# SCH_esig_2025-06-15.net
KiCad netlist of a schematic drawn in EasyEDA
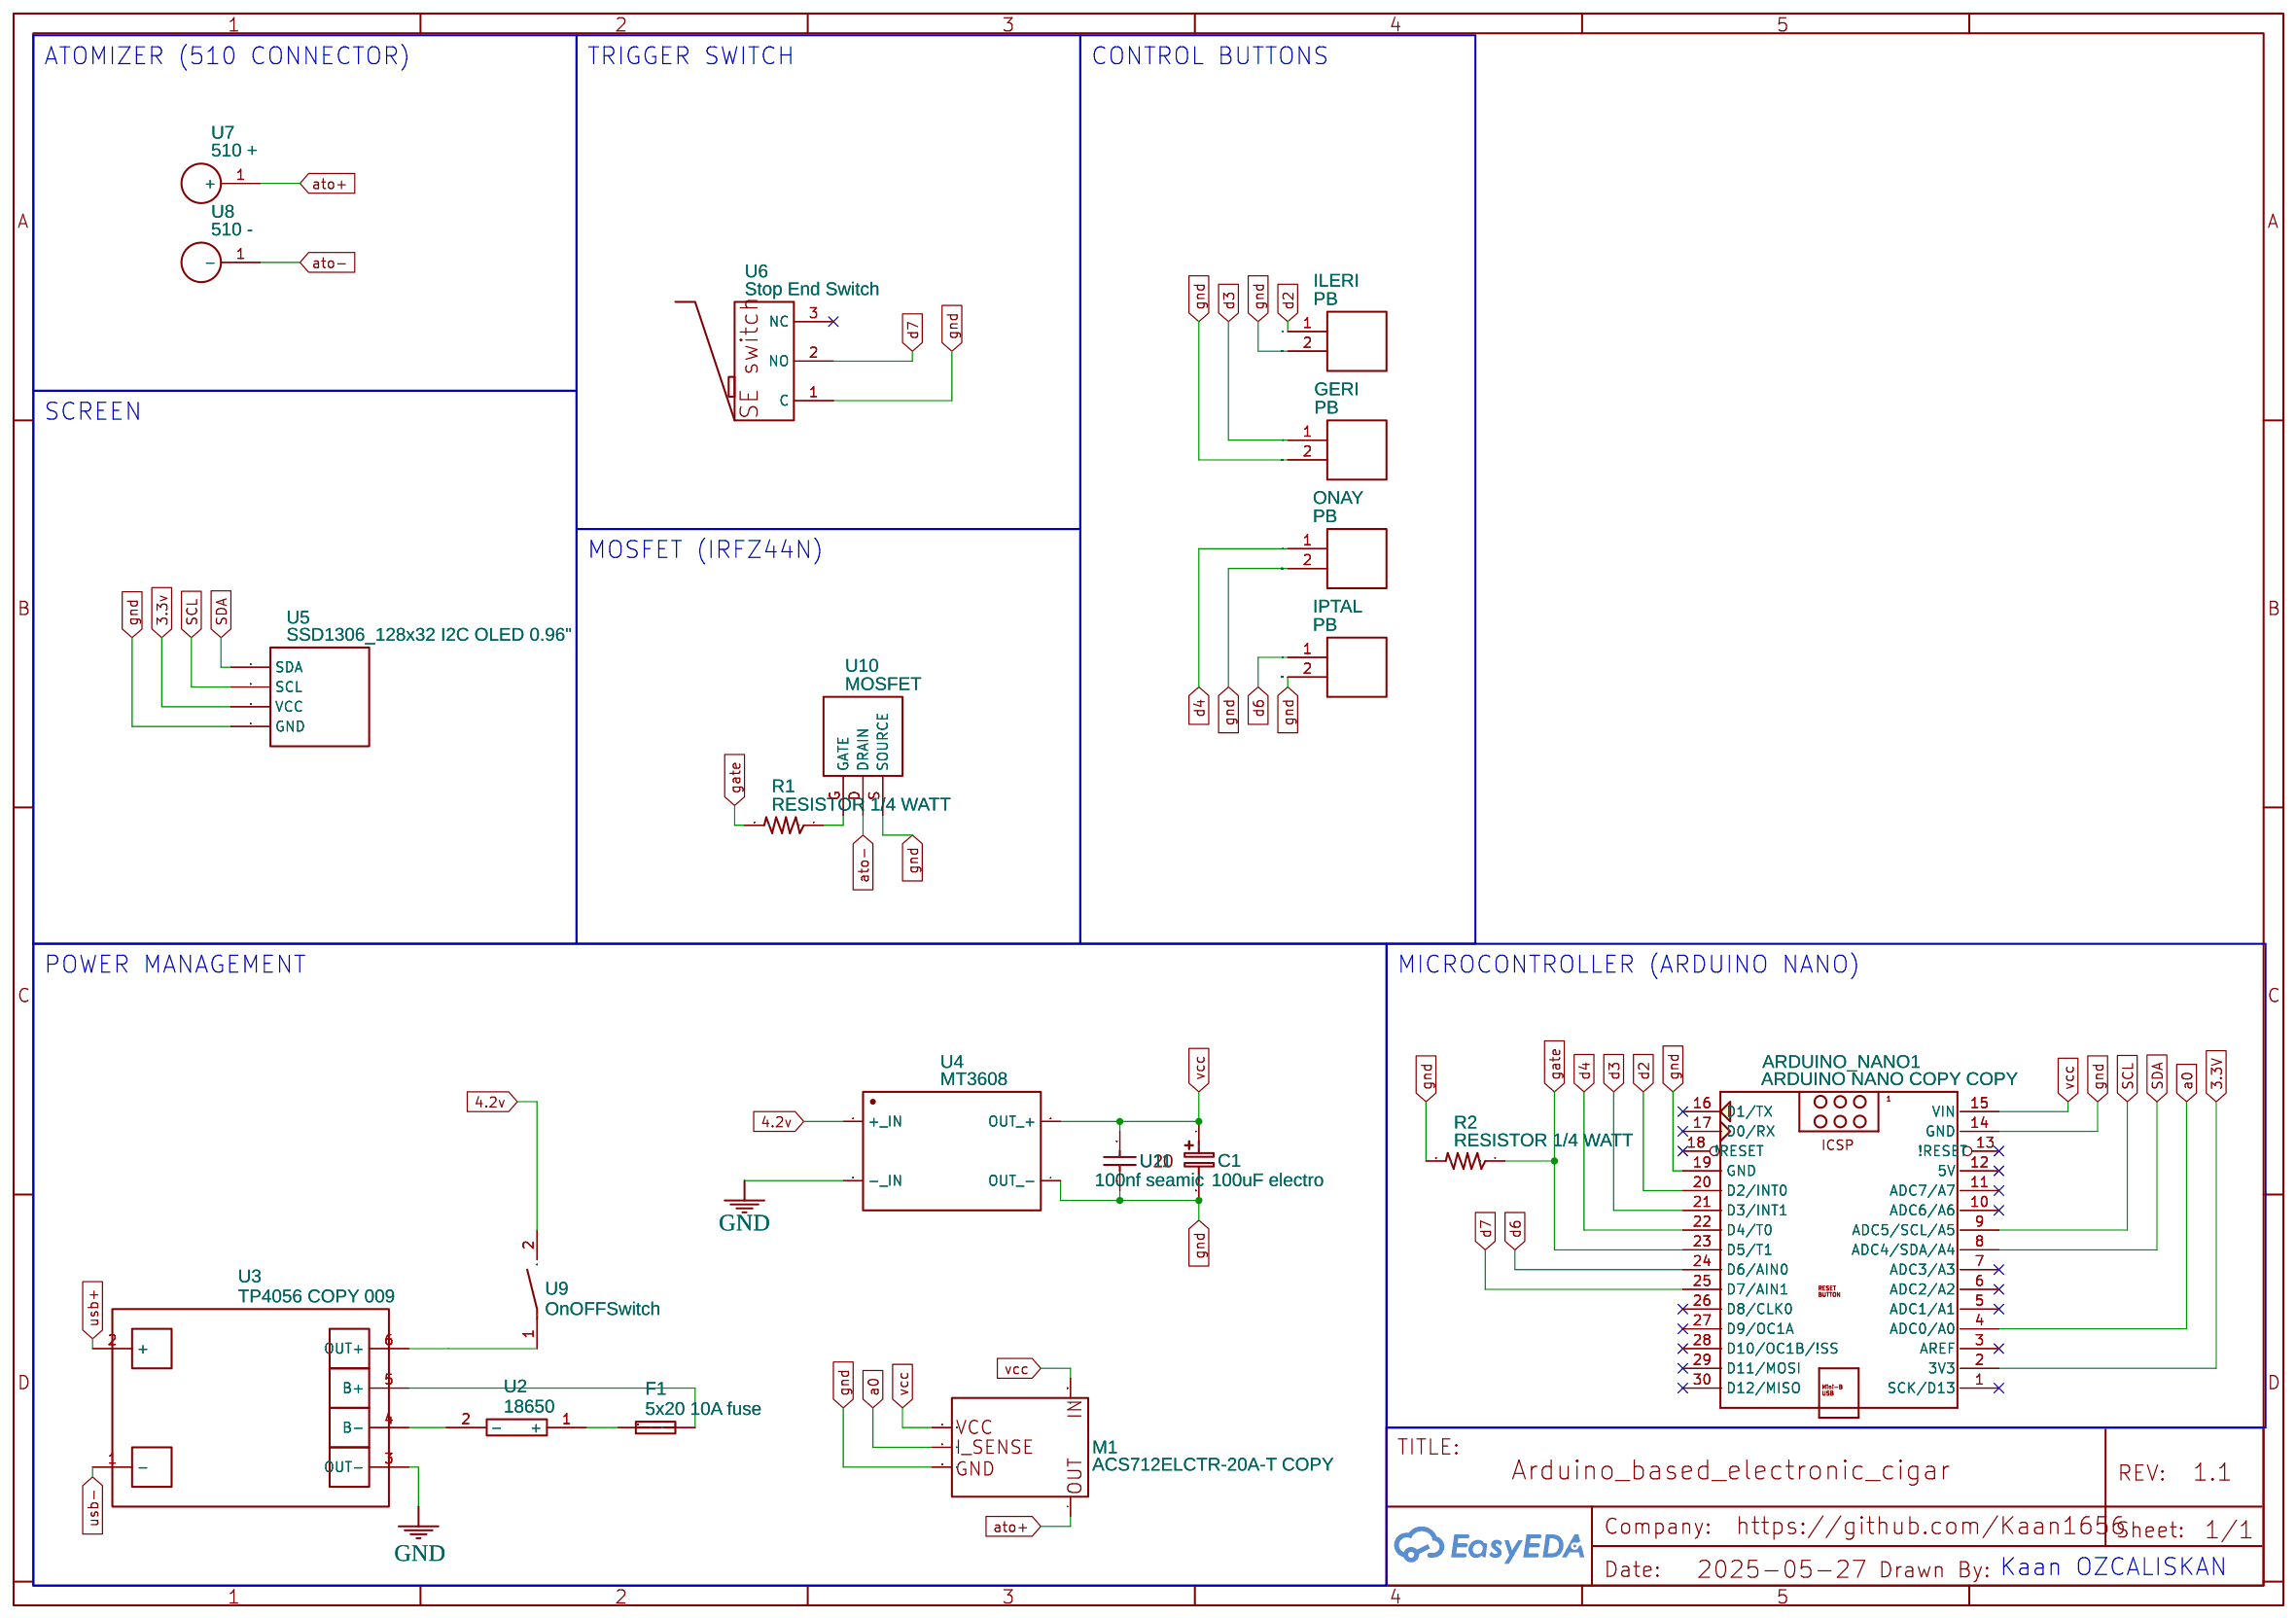
[diagram p0: schematic sheet]

(export (version "E")
  (design (tool "Eeschema 10.0.6"))
  (components
    (comp (ref "ARDUINO_NANO1")
      (value "ARDUINO NANO COPY COPY")
      (libsource (lib "") (part "ARDUINO NANO COPY COPY"))
    )
    (comp (ref "C1") (value "100uF electro") (libsource (lib "") (part "ELECTROLITIC_10MM_20.5MM")))
    (comp (ref "F1") (value "5x20 10A fuse") (libsource (lib "") (part "GLASS_FUSE_5X20")))
    (comp (ref "GERI") (value "PB") (libsource (lib "") (part "MY pushbutton_3")))
    (comp (ref "ILERI") (value "PB") (libsource (lib "") (part "MY pushbutton_2")))
    (comp (ref "IPTAL") (value "PB") (libsource (lib "") (part "MY pushbutton_1")))
    (comp (ref "M1") (value "ACS712ELCTR-20A-T COPY") (libsource (lib "") (part "ACS712ELCTR-20A-T COPY")))
    (comp (ref "ONAY") (value "PB") (libsource (lib "") (part "MY pushbutton")))
    (comp (ref "R1") (value "RESISTOR 1/4 WATT") (libsource (lib "") (part "RESISTOR 1/4 WATT TH Ω")))
    (comp (ref "R2") (value "RESISTOR 1/4 WATT") (libsource (lib "") (part "RESISTOR 1/4 WATT TH Ω")))
    (comp (ref "U2") (value "18650") (libsource (lib "") (part "18650_Mount")))
    (comp (ref "U3") (value "TP4056 COPY 009") (libsource (lib "") (part "TP4056 COPY 009")))
    (comp (ref "U4")
      (value "MT3608")
      (fields
        (field (name "Manufacturer Part") "MT3806 DC-DC Step Up")
        (field (name "Manufacturer") "NoName")
      )
      (libsource (lib "") (part "MT3806"))
    )
    (comp (ref "U5")
      (value "SSD1306_128x32 I2C OLED 0.96\"")
      (libsource (lib "") (part "SSD1306_128x32 I2C OLED 0.96{dblquote}"))
    )
    (comp (ref "U6") (value "Stop End Switch") (libsource (lib "") (part "Stop End Switch")))
    (comp (ref "U7") (value "510 +") (libsource (lib "") (part "wire hole 20AWG")))
    (comp (ref "U8") (value "510 -") (libsource (lib "") (part "wire hole 20AWG_1")))
    (comp (ref "U9") (value "OnOFFSwitch") (libsource (lib "") (part "OnOFFSwitch")))
    (comp (ref "U10") (value "MOSFET") (libsource (lib "") (part "MOSFET")))
    (comp (ref "U11") (value "100nf seamic") (libsource (lib "") (part "Large seramic capacitor")))
  )
  (nets
    (net (code "1") (name "3.3V") (class "Default")
      (node (ref "ARDUINO_NANO1") (pin "2") (pinfunction "3V3_2") (pintype "bidirectional"))
    )
    (net (code "2") (name "3.3v") (class "Default")
      (node (ref "U5") (pin "3") (pinfunction "VCC_3") (pintype "unspecified"))
    )
    (net (code "3") (name "4.2v") (class "Default")
      (node (ref "U4") (pin "1") (pinfunction "+_IN_1") (pintype "unspecified"))
      (node (ref "U9") (pin "2") (pinfunction "2_2") (pintype "unspecified"))
    )
    (net (code "4") (name "GND") (class "Default")
      (node (ref "U3") (pin "3") (pinfunction "OUT-_3") (pintype "unspecified"))
      (node (ref "U4") (pin "2") (pinfunction "-_IN_2") (pintype "unspecified"))
    )
    (net (code "5") (name "Net-(U2-+)") (class "Default")
      (node (ref "F1") (pin "2") (pinfunction "2_2") (pintype "unspecified"))
      (node (ref "U2") (pin "1") (pinfunction "+_1") (pintype "unspecified"))
    )
    (net (code "6") (name "Net-(U2--)") (class "Default")
      (node (ref "U2") (pin "2") (pinfunction "-_2") (pintype "unspecified"))
      (node (ref "U3") (pin "4") (pinfunction "B-_4") (pintype "unspecified"))
    )
    (net (code "7") (name "Net-(U3-B+)") (class "Default")
      (node (ref "F1") (pin "1") (pinfunction "1_1") (pintype "unspecified"))
      (node (ref "U3") (pin "5") (pinfunction "B+_5") (pintype "unspecified"))
    )
    (net (code "8") (name "Net-(U3-OUT+)") (class "Default")
      (node (ref "U3") (pin "6") (pinfunction "OUT+_6") (pintype "unspecified"))
      (node (ref "U9") (pin "1") (pinfunction "1_1") (pintype "unspecified"))
    )
    (net (code "9") (name "Net-(U10-GATE)") (class "Default")
      (node (ref "R1") (pin "1") (pinfunction "1_1") (pintype "unspecified"))
      (node (ref "U10") (pin "G") (pinfunction "GATE_G") (pintype "unspecified"))
    )
    (net (code "10") (name "SCL") (class "Default")
      (node (ref "ARDUINO_NANO1") (pin "9") (pinfunction "ADC5/SCL/A5_9") (pintype "bidirectional"))
      (node (ref "U5") (pin "2") (pinfunction "SCL_2") (pintype "unspecified"))
    )
    (net (code "11") (name "SDA") (class "Default")
      (node (ref "ARDUINO_NANO1") (pin "8") (pinfunction "ADC4/SDA/A4_8") (pintype "bidirectional"))
      (node (ref "U5") (pin "1") (pinfunction "SDA_1") (pintype "unspecified"))
    )
    (net (code "12") (name "a0") (class "Default")
      (node (ref "ARDUINO_NANO1") (pin "4") (pinfunction "ADC0/A0_4") (pintype "bidirectional"))
      (node (ref "M1") (pin "2") (pinfunction "4_2") (pintype "unspecified"))
    )
    (net (code "13") (name "ato+") (class "Default")
      (node (ref "M1") (pin "4") (pinfunction "2_4") (pintype "unspecified"))
      (node (ref "U7") (pin "1") (pinfunction "+_1") (pintype "unspecified"))
    )
    (net (code "14") (name "ato-") (class "Default")
      (node (ref "U10") (pin "D") (pinfunction "DRAIN_D") (pintype "unspecified"))
      (node (ref "U8") (pin "1") (pinfunction "-_1") (pintype "unspecified"))
    )
    (net (code "15") (name "d2") (class "Default")
      (node (ref "ARDUINO_NANO1") (pin "20") (pinfunction "D2/INT0_20") (pintype "bidirectional"))
      (node (ref "ILERI") (pin "1") (pinfunction "1_1") (pintype "unspecified"))
    )
    (net (code "16") (name "d3") (class "Default")
      (node (ref "ARDUINO_NANO1") (pin "21") (pinfunction "D3/INT1_21") (pintype "bidirectional"))
      (node (ref "GERI") (pin "1") (pinfunction "1_1") (pintype "unspecified"))
    )
    (net (code "17") (name "d4") (class "Default")
      (node (ref "ARDUINO_NANO1") (pin "22") (pinfunction "D4/T0_22") (pintype "bidirectional"))
      (node (ref "ONAY") (pin "1") (pinfunction "1_1") (pintype "unspecified"))
    )
    (net (code "18") (name "d6") (class "Default")
      (node (ref "ARDUINO_NANO1") (pin "24") (pinfunction "D6/AIN0_24") (pintype "bidirectional"))
      (node (ref "IPTAL") (pin "1") (pinfunction "1_1") (pintype "unspecified"))
    )
    (net (code "19") (name "d7") (class "Default")
      (node (ref "ARDUINO_NANO1") (pin "25") (pinfunction "D7/AIN1_25") (pintype "bidirectional"))
      (node (ref "U6") (pin "2") (pinfunction "NO_2") (pintype "unspecified"))
    )
    (net (code "20") (name "gate") (class "Default")
      (node (ref "ARDUINO_NANO1") (pin "23") (pinfunction "D5/T1_23") (pintype "bidirectional"))
      (node (ref "R1") (pin "2") (pinfunction "2_2") (pintype "unspecified"))
      (node (ref "R2") (pin "1") (pinfunction "1_1") (pintype "unspecified"))
    )
    (net (code "21") (name "gnd") (class "Default")
      (node (ref "ARDUINO_NANO1") (pin "14") (pinfunction "GND_14") (pintype "bidirectional"))
      (node (ref "ARDUINO_NANO1") (pin "19") (pinfunction "GND_19") (pintype "bidirectional"))
      (node (ref "C1") (pin "2") (pinfunction "2_2") (pintype "unspecified"))
      (node (ref "GERI") (pin "2") (pinfunction "Pushbutton_2") (pintype "unspecified"))
      (node (ref "ILERI") (pin "2") (pinfunction "Pushbutton_2") (pintype "unspecified"))
      (node (ref "IPTAL") (pin "2") (pinfunction "Pushbutton_2") (pintype "unspecified"))
      (node (ref "M1") (pin "3") (pinfunction "5_3") (pintype "unspecified"))
      (node (ref "ONAY") (pin "2") (pinfunction "Pushbutton_2") (pintype "unspecified"))
      (node (ref "R2") (pin "2") (pinfunction "2_2") (pintype "unspecified"))
      (node (ref "U10") (pin "S") (pinfunction "SOURCE_S") (pintype "unspecified"))
      (node (ref "U11") (pin "1") (pinfunction "1_1") (pintype "input"))
      (node (ref "U4") (pin "4") (pinfunction "OUT_-_4") (pintype "unspecified"))
      (node (ref "U5") (pin "4") (pinfunction "GND_4") (pintype "unspecified"))
      (node (ref "U6") (pin "1") (pinfunction "C_1") (pintype "unspecified"))
    )
    (net (code "22") (name "unconnected-(ARDUINO_NANO1-!RESET-Pad13)") (class "Default")
      (node (ref "ARDUINO_NANO1") (pin "13") (pinfunction "!RESET_13") (pintype "bidirectional+no_connect"))
    )
    (net (code "23") (name "unconnected-(ARDUINO_NANO1-!RESET-Pad18)") (class "Default")
      (node (ref "ARDUINO_NANO1") (pin "18") (pinfunction "!RESET_18") (pintype "bidirectional+no_connect"))
    )
    (net (code "24") (name "unconnected-(ARDUINO_NANO1-5V-Pad12)") (class "Default")
      (node (ref "ARDUINO_NANO1") (pin "12") (pinfunction "5V_12") (pintype "bidirectional+no_connect"))
    )
    (net (code "25") (name "unconnected-(ARDUINO_NANO1-ADC1{slash}A1-Pad5)") (class "Default")
      (node (ref "ARDUINO_NANO1") (pin "5") (pinfunction "ADC1/A1_5") (pintype "bidirectional+no_connect"))
    )
    (net (code "26") (name "unconnected-(ARDUINO_NANO1-ADC2{slash}A2-Pad6)") (class "Default")
      (node (ref "ARDUINO_NANO1") (pin "6") (pinfunction "ADC2/A2_6") (pintype "bidirectional+no_connect"))
    )
    (net (code "27") (name "unconnected-(ARDUINO_NANO1-ADC3{slash}A3-Pad7)") (class "Default")
      (node (ref "ARDUINO_NANO1") (pin "7") (pinfunction "ADC3/A3_7") (pintype "bidirectional+no_connect"))
    )
    (net (code "28") (name "unconnected-(ARDUINO_NANO1-ADC6{slash}A6-Pad10)") (class "Default")
      (node (ref "ARDUINO_NANO1") (pin "10") (pinfunction "ADC6/A6_10") (pintype "bidirectional+no_connect"))
    )
    (net (code "29") (name "unconnected-(ARDUINO_NANO1-ADC7{slash}A7-Pad11)") (class "Default")
      (node (ref "ARDUINO_NANO1") (pin "11") (pinfunction "ADC7/A7_11") (pintype "bidirectional+no_connect"))
    )
    (net (code "30") (name "unconnected-(ARDUINO_NANO1-AREF-Pad3)") (class "Default")
      (node (ref "ARDUINO_NANO1") (pin "3") (pinfunction "AREF_3") (pintype "bidirectional+no_connect"))
    )
    (net (code "31") (name "unconnected-(ARDUINO_NANO1-D0{slash}RX-Pad17)") (class "Default")
      (node (ref "ARDUINO_NANO1") (pin "17") (pinfunction "D0/RX_17") (pintype "bidirectional+no_connect"))
    )
    (net (code "32") (name "unconnected-(ARDUINO_NANO1-D1{slash}TX-Pad16)") (class "Default")
      (node (ref "ARDUINO_NANO1") (pin "16") (pinfunction "D1/TX_16") (pintype "bidirectional+no_connect"))
    )
    (net (code "33") (name "unconnected-(ARDUINO_NANO1-D8{slash}CLK0-Pad26)") (class "Default")
      (node (ref "ARDUINO_NANO1") (pin "26") (pinfunction "D8/CLK0_26") (pintype "bidirectional+no_connect"))
    )
    (net (code "34") (name "unconnected-(ARDUINO_NANO1-D9{slash}OC1A-Pad27)") (class "Default")
      (node (ref "ARDUINO_NANO1") (pin "27") (pinfunction "D9/OC1A_27") (pintype "bidirectional+no_connect"))
    )
    (net (code "35") (name "unconnected-(ARDUINO_NANO1-D10{slash}OC1B{slash}!SS-Pad28)") (class "Default")
      (node (ref "ARDUINO_NANO1") (pin "28") (pinfunction "D10/OC1B/!SS_28") (pintype "bidirectional+no_connect"))
    )
    (net (code "36") (name "unconnected-(ARDUINO_NANO1-D11{slash}MOSI-Pad29)") (class "Default")
      (node (ref "ARDUINO_NANO1") (pin "29") (pinfunction "D11/MOSI_29") (pintype "bidirectional+no_connect"))
    )
    (net (code "37") (name "unconnected-(ARDUINO_NANO1-D12{slash}MISO-Pad30)") (class "Default")
      (node (ref "ARDUINO_NANO1") (pin "30") (pinfunction "D12/MISO_30") (pintype "bidirectional+no_connect"))
    )
    (net (code "38") (name "unconnected-(ARDUINO_NANO1-SCK{slash}D13-Pad1)") (class "Default")
      (node (ref "ARDUINO_NANO1") (pin "1") (pinfunction "SCK/D13_1") (pintype "bidirectional+no_connect"))
    )
    (net (code "39") (name "unconnected-(U6-NC-Pad3)") (class "Default")
      (node (ref "U6") (pin "3") (pinfunction "NC_3") (pintype "unspecified+no_connect"))
    )
    (net (code "40") (name "usb+") (class "Default")
      (node (ref "U3") (pin "2") (pinfunction "+_2") (pintype "unspecified"))
    )
    (net (code "41") (name "usb-") (class "Default")
      (node (ref "U3") (pin "1") (pinfunction "-_1") (pintype "unspecified"))
    )
    (net (code "42") (name "vcc") (class "Default")
      (node (ref "ARDUINO_NANO1") (pin "15") (pinfunction "VIN_15") (pintype "bidirectional"))
      (node (ref "C1") (pin "1") (pinfunction "1_1") (pintype "unspecified"))
      (node (ref "M1") (pin "1") (pinfunction "3_1") (pintype "unspecified"))
      (node (ref "M1") (pin "5") (pinfunction "1_5") (pintype "unspecified"))
      (node (ref "U11") (pin "2") (pinfunction "2_2") (pintype "input"))
      (node (ref "U4") (pin "3") (pinfunction "OUT_+_3") (pintype "unspecified"))
    )
  )
)
